# PCB-RPIBO1_HDMIEXT.net
KiCad netlist of a schematic drawn in EAGLE
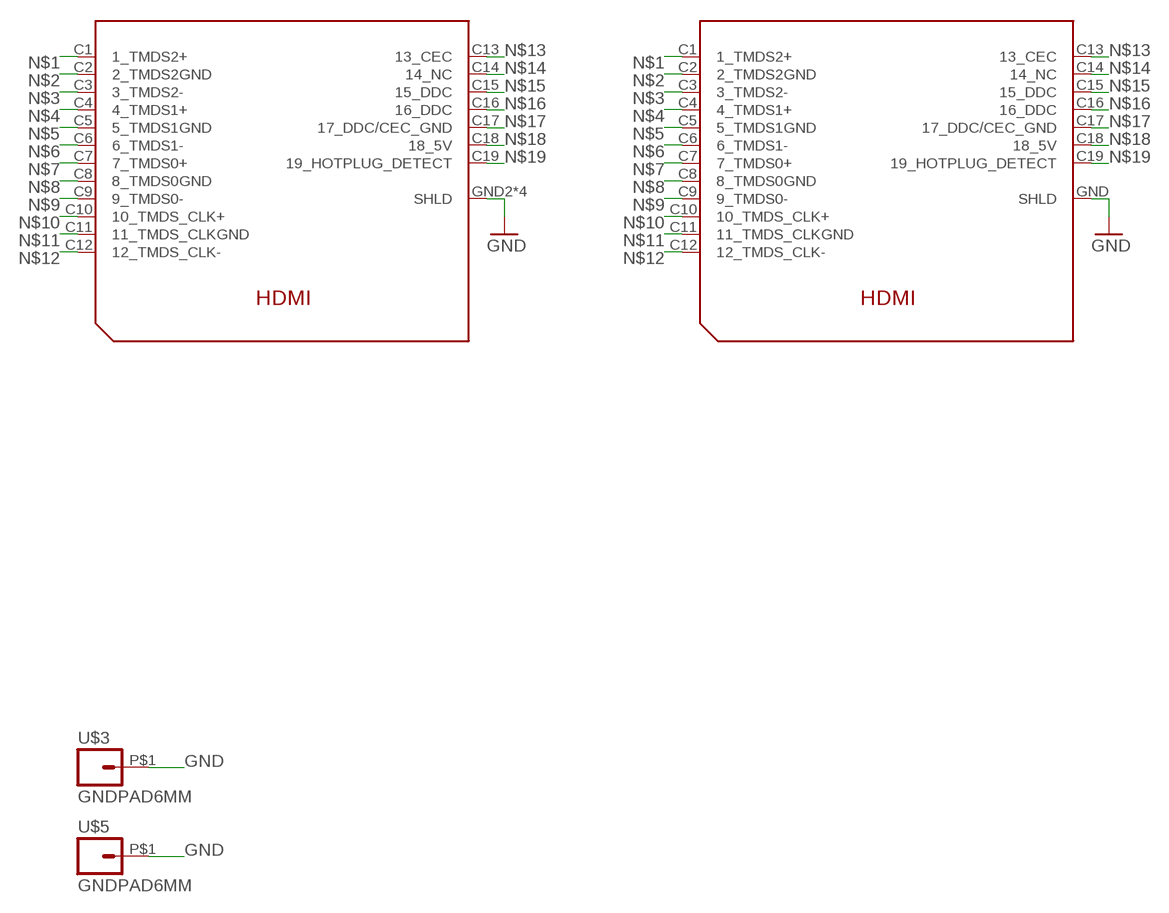
[diagram p0: schematic, sheet 1]

(export (version "E")
  (design (tool "Eeschema 10.0.6"))
  (components
    (comp (ref "U$1")
      (value "HDMI")
      (footprint "eagle-import:HDMI")
      (libsource (lib "eagle-import") (part "HDMI"))
    )
    (comp (ref "U$2")
      (value "HDMIPCBMALECON")
      (footprint "eagle-import:HDMI_MALEINTERCON")
      (libsource (lib "eagle-import") (part "HDMIPCBMALECON"))
    )
    (comp (ref "U$3")
      (value "GNDPAD6MM")
      (footprint "eagle-import:3.2MMPAD6MM")
      (libsource (lib "eagle-import") (part "GNDPAD6MM"))
    )
    (comp (ref "U$5")
      (value "GNDPAD6MM")
      (footprint "eagle-import:3.2MMPAD6MM")
      (libsource (lib "eagle-import") (part "GNDPAD6MM"))
    )
  )
  (nets
    (net (code "1") (name "GND") (class "Default")
      (node (ref "U$1") (pin "GND2") (pinfunction "SHLD_GND2") (pintype "bidirectional"))
      (node (ref "U$1") (pin "GND3") (pinfunction "SHLD_GND3") (pintype "bidirectional"))
      (node (ref "U$1") (pin "P$2") (pinfunction "SHLD_P$2") (pintype "bidirectional"))
      (node (ref "U$1") (pin "P$3") (pinfunction "SHLD_P$3") (pintype "bidirectional"))
      (node (ref "U$2") (pin "GND") (pinfunction "SHLD_GND") (pintype "bidirectional"))
      (node (ref "U$3") (pin "P$1") (pinfunction "1_P$1") (pintype "passive"))
      (node (ref "U$5") (pin "P$1") (pinfunction "1_P$1") (pintype "passive"))
    )
    (net (code "2") (name "N$1") (class "Default")
      (node (ref "U$1") (pin "C1") (pinfunction "1_TMDS2+_C1") (pintype "bidirectional"))
      (node (ref "U$2") (pin "C1") (pinfunction "1_TMDS2+_C1") (pintype "bidirectional"))
    )
    (net (code "3") (name "N$2") (class "Default")
      (node (ref "U$1") (pin "C2") (pinfunction "2_TMDS2GND_C2") (pintype "bidirectional"))
      (node (ref "U$2") (pin "C2") (pinfunction "2_TMDS2GND_C2") (pintype "bidirectional"))
    )
    (net (code "4") (name "N$3") (class "Default")
      (node (ref "U$1") (pin "C3") (pinfunction "3_TMDS2-_C3") (pintype "bidirectional"))
      (node (ref "U$2") (pin "C3") (pinfunction "3_TMDS2-_C3") (pintype "bidirectional"))
    )
    (net (code "5") (name "N$4") (class "Default")
      (node (ref "U$1") (pin "C4") (pinfunction "4_TMDS1+_C4") (pintype "bidirectional"))
      (node (ref "U$2") (pin "C4") (pinfunction "4_TMDS1+_C4") (pintype "bidirectional"))
    )
    (net (code "6") (name "N$5") (class "Default")
      (node (ref "U$1") (pin "C5") (pinfunction "5_TMDS1GND_C5") (pintype "bidirectional"))
      (node (ref "U$2") (pin "C5") (pinfunction "5_TMDS1GND_C5") (pintype "bidirectional"))
    )
    (net (code "7") (name "N$6") (class "Default")
      (node (ref "U$1") (pin "C6") (pinfunction "6_TMDS1-_C6") (pintype "bidirectional"))
      (node (ref "U$2") (pin "C6") (pinfunction "6_TMDS1-_C6") (pintype "bidirectional"))
    )
    (net (code "8") (name "N$7") (class "Default")
      (node (ref "U$1") (pin "C7") (pinfunction "7_TMDS0+_C7") (pintype "bidirectional"))
      (node (ref "U$2") (pin "C7") (pinfunction "7_TMDS0+_C7") (pintype "bidirectional"))
    )
    (net (code "9") (name "N$8") (class "Default")
      (node (ref "U$1") (pin "C8") (pinfunction "8_TMDS0GND_C8") (pintype "bidirectional"))
      (node (ref "U$2") (pin "C8") (pinfunction "8_TMDS0GND_C8") (pintype "bidirectional"))
    )
    (net (code "10") (name "N$9") (class "Default")
      (node (ref "U$1") (pin "C9") (pinfunction "9_TMDS0-_C9") (pintype "bidirectional"))
      (node (ref "U$2") (pin "C9") (pinfunction "9_TMDS0-_C9") (pintype "bidirectional"))
    )
    (net (code "11") (name "N$10") (class "Default")
      (node (ref "U$1") (pin "C10") (pinfunction "10_TMDS_CLK+_C10") (pintype "bidirectional"))
      (node (ref "U$2") (pin "C10") (pinfunction "10_TMDS_CLK+_C10") (pintype "bidirectional"))
    )
    (net (code "12") (name "N$11") (class "Default")
      (node (ref "U$1") (pin "C11") (pinfunction "11_TMDS_CLKGND_C11") (pintype "bidirectional"))
      (node (ref "U$2") (pin "C11") (pinfunction "11_TMDS_CLKGND_C11") (pintype "bidirectional"))
    )
    (net (code "13") (name "N$12") (class "Default")
      (node (ref "U$1") (pin "C12") (pinfunction "12_TMDS_CLK-_C12") (pintype "bidirectional"))
      (node (ref "U$2") (pin "C12") (pinfunction "12_TMDS_CLK-_C12") (pintype "bidirectional"))
    )
    (net (code "14") (name "N$13") (class "Default")
      (node (ref "U$1") (pin "C13") (pinfunction "13_CEC_C13") (pintype "bidirectional"))
      (node (ref "U$2") (pin "C13") (pinfunction "13_CEC_C13") (pintype "bidirectional"))
    )
    (net (code "15") (name "N$14") (class "Default")
      (node (ref "U$1") (pin "C14") (pinfunction "14_NC_C14") (pintype "bidirectional"))
      (node (ref "U$2") (pin "C14") (pinfunction "14_NC_C14") (pintype "bidirectional"))
    )
    (net (code "16") (name "N$15") (class "Default")
      (node (ref "U$1") (pin "C15") (pinfunction "15_DDC_C15") (pintype "bidirectional"))
      (node (ref "U$2") (pin "C15") (pinfunction "15_DDC_C15") (pintype "bidirectional"))
    )
    (net (code "17") (name "N$16") (class "Default")
      (node (ref "U$1") (pin "C16") (pinfunction "16_DDC_C16") (pintype "bidirectional"))
      (node (ref "U$2") (pin "C16") (pinfunction "16_DDC_C16") (pintype "bidirectional"))
    )
    (net (code "18") (name "N$17") (class "Default")
      (node (ref "U$1") (pin "C17") (pinfunction "17_DDC/CEC_GND_C17") (pintype "bidirectional"))
      (node (ref "U$2") (pin "C17") (pinfunction "17_DDC/CEC_GND_C17") (pintype "bidirectional"))
    )
    (net (code "19") (name "N$18") (class "Default")
      (node (ref "U$1") (pin "C18") (pinfunction "18_5V_C18") (pintype "bidirectional"))
      (node (ref "U$2") (pin "C18") (pinfunction "18_5V_C18") (pintype "bidirectional"))
    )
    (net (code "20") (name "N$19") (class "Default")
      (node (ref "U$1") (pin "C19") (pinfunction "19_HOTPLUG_DETECT_C19") (pintype "bidirectional"))
      (node (ref "U$2") (pin "C19") (pinfunction "19_HOTPLUG_DETECT_C19") (pintype "bidirectional"))
    )
  )
)
